# NT_SolarModule3.net
KiCad netlist of a schematic drawn in EAGLE
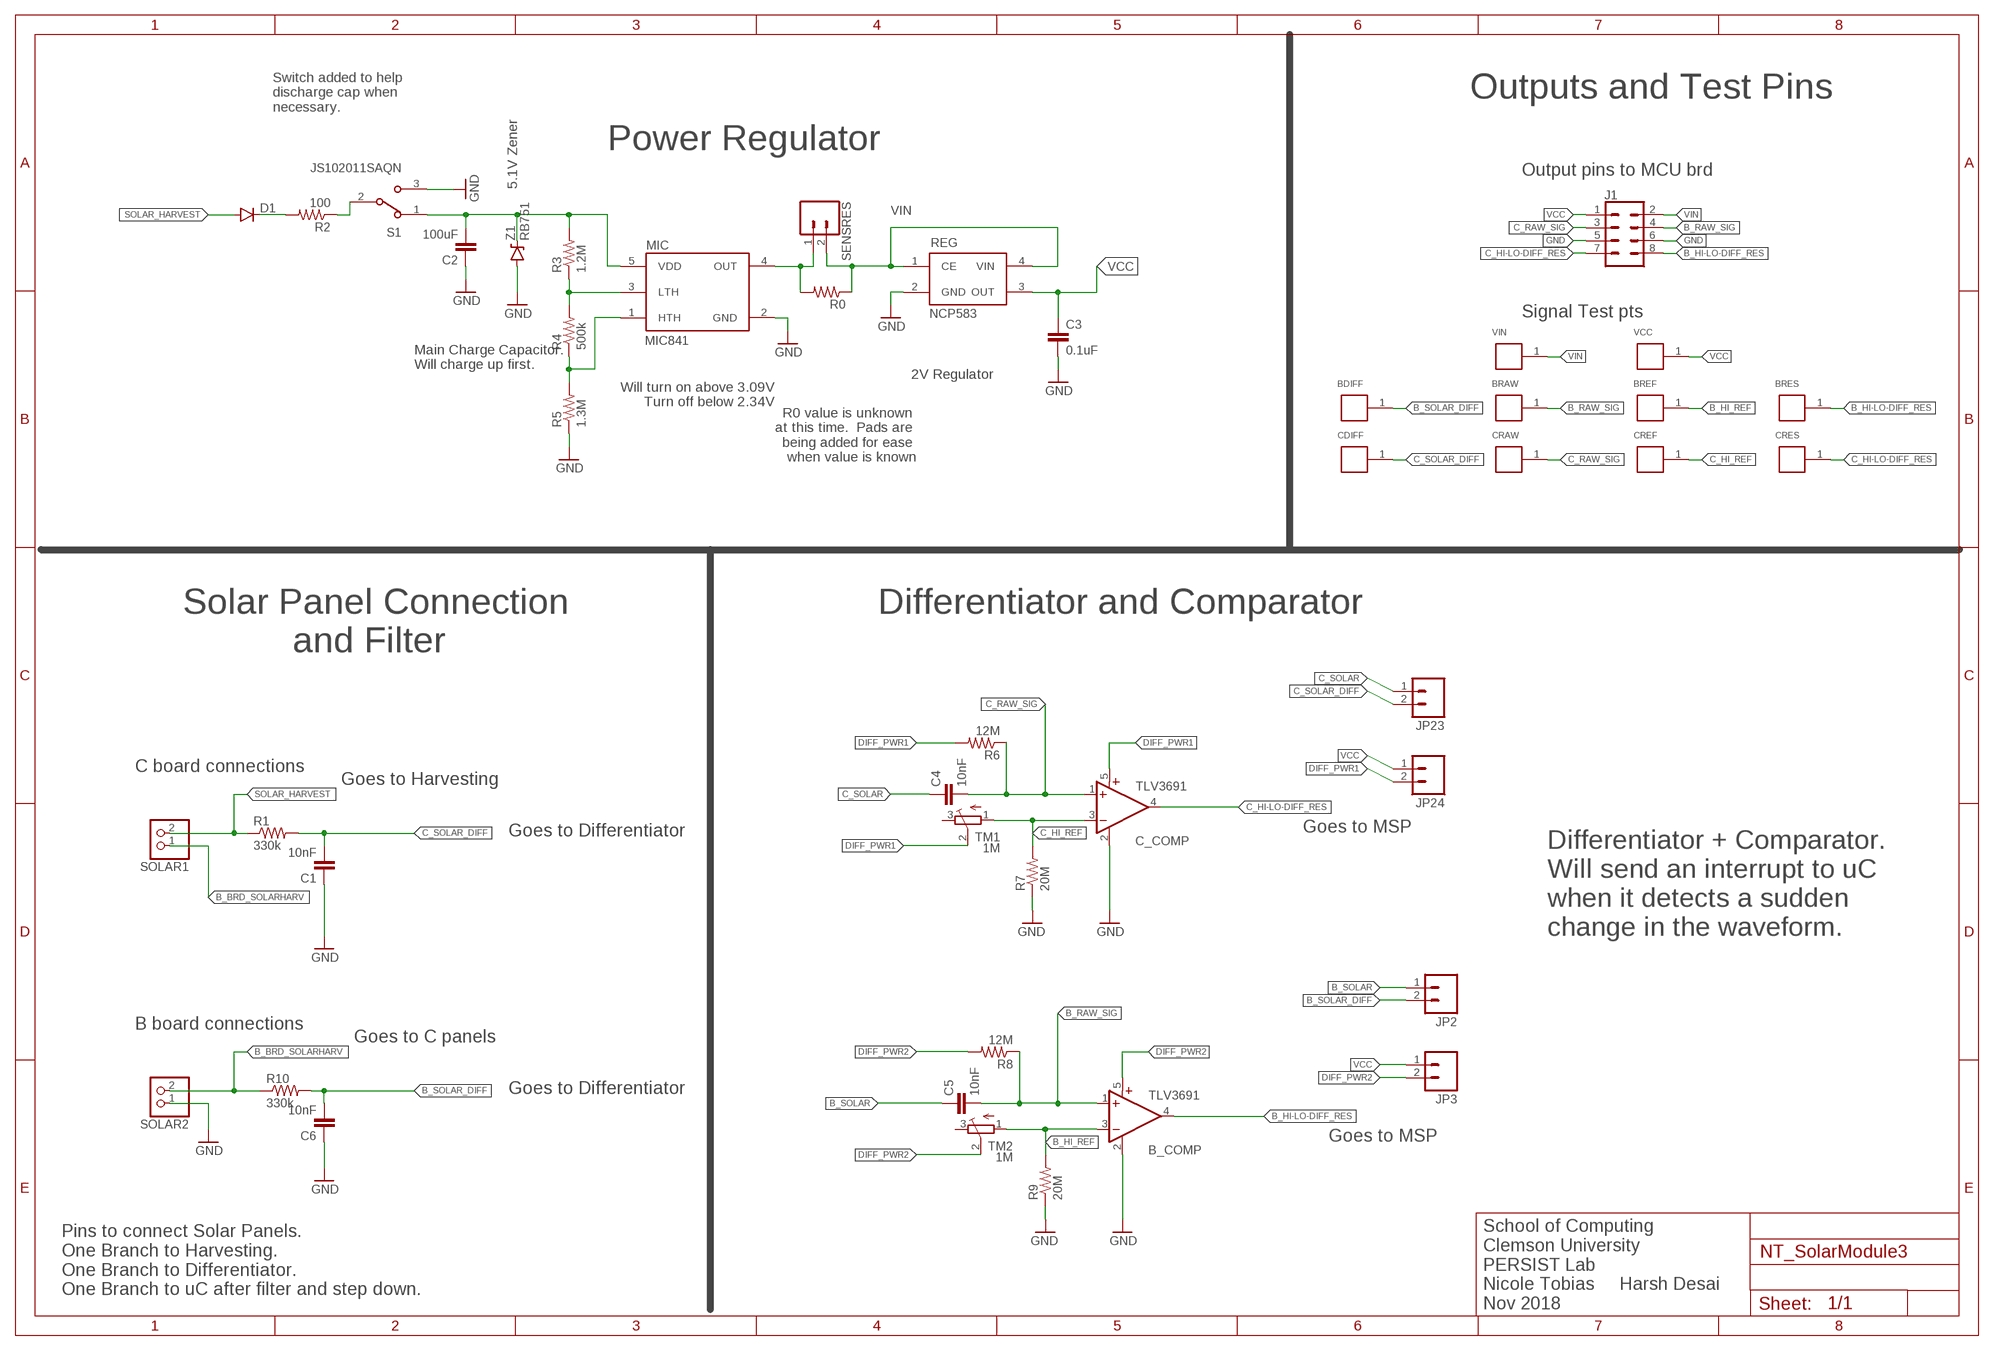
[diagram p0: schematic, sheet 1]

(export (version "E")
  (design (tool "Eeschema 10.0.6"))
  (components
    (comp (ref "BDIFF")
      (value "RCU-0C")
      (footprint "eagle-import:TE_RCU-0C")
      (fields
        (field (name "COMMENT") "RCU-0C _1625854-3_")
        (field (name "MF") "TE Connectivity")
        (field (name "TOLERANCE") "0%")
      )
      (libsource (lib "eagle-import") (part "RCU-0C"))
    )
    (comp (ref "BRAW")
      (value "RCU-0C")
      (footprint "eagle-import:TE_RCU-0C")
      (fields
        (field (name "COMMENT") "RCU-0C _1625854-3_")
        (field (name "MF") "TE Connectivity")
        (field (name "TOLERANCE") "0%")
      )
      (libsource (lib "eagle-import") (part "RCU-0C"))
    )
    (comp (ref "BREF")
      (value "RCU-0C")
      (footprint "eagle-import:TE_RCU-0C")
      (fields
        (field (name "COMMENT") "RCU-0C _1625854-3_")
        (field (name "MF") "TE Connectivity")
        (field (name "TOLERANCE") "0%")
      )
      (libsource (lib "eagle-import") (part "RCU-0C"))
    )
    (comp (ref "BRES")
      (value "RCU-0C")
      (footprint "eagle-import:TE_RCU-0C")
      (fields
        (field (name "COMMENT") "RCU-0C _1625854-3_")
        (field (name "MF") "TE Connectivity")
        (field (name "TOLERANCE") "0%")
      )
      (libsource (lib "eagle-import") (part "RCU-0C"))
    )
    (comp (ref "B_COMP")
      (value "TLV3691")
      (footprint "eagle-import:SC70-5")
      (libsource (lib "eagle-import") (part "TLV3691"))
    )
    (comp (ref "C1")
      (value "10nF")
      (footprint "eagle-import:0603-CAP")
      (libsource (lib "eagle-import") (part "CAP0603-CAP"))
    )
    (comp (ref "C2")
      (value "100uF")
      (footprint "eagle-import:0603-CAP")
      (libsource (lib "eagle-import") (part "CAP0603-CAP"))
    )
    (comp (ref "C3")
      (value "0.1uF")
      (footprint "eagle-import:0603-CAP")
      (libsource (lib "eagle-import") (part "CAP0603-CAP"))
    )
    (comp (ref "C4")
      (value "10nF")
      (footprint "eagle-import:0603-CAP")
      (libsource (lib "eagle-import") (part "CAP0603-CAP"))
    )
    (comp (ref "C5")
      (value "10nF")
      (footprint "eagle-import:0603-CAP")
      (libsource (lib "eagle-import") (part "CAP0603-CAP"))
    )
    (comp (ref "C6")
      (value "10nF")
      (footprint "eagle-import:0603-CAP")
      (libsource (lib "eagle-import") (part "CAP0603-CAP"))
    )
    (comp (ref "CDIFF")
      (value "RCU-0C")
      (footprint "eagle-import:TE_RCU-0C")
      (fields
        (field (name "COMMENT") "RCU-0C _1625854-3_")
        (field (name "MF") "TE Connectivity")
        (field (name "TOLERANCE") "0%")
      )
      (libsource (lib "eagle-import") (part "RCU-0C"))
    )
    (comp (ref "CRAW")
      (value "RCU-0C")
      (footprint "eagle-import:TE_RCU-0C")
      (fields
        (field (name "COMMENT") "RCU-0C _1625854-3_")
        (field (name "MF") "TE Connectivity")
        (field (name "TOLERANCE") "0%")
      )
      (libsource (lib "eagle-import") (part "RCU-0C"))
    )
    (comp (ref "CREF")
      (value "RCU-0C")
      (footprint "eagle-import:TE_RCU-0C")
      (fields
        (field (name "COMMENT") "RCU-0C _1625854-3_")
        (field (name "MF") "TE Connectivity")
        (field (name "TOLERANCE") "0%")
      )
      (libsource (lib "eagle-import") (part "RCU-0C"))
    )
    (comp (ref "CRES")
      (value "RCU-0C")
      (footprint "eagle-import:TE_RCU-0C")
      (fields
        (field (name "COMMENT") "RCU-0C _1625854-3_")
        (field (name "MF") "TE Connectivity")
        (field (name "TOLERANCE") "0%")
      )
      (libsource (lib "eagle-import") (part "RCU-0C"))
    )
    (comp (ref "C_COMP")
      (value "TLV3691")
      (footprint "eagle-import:SC70-5")
      (libsource (lib "eagle-import") (part "TLV3691"))
    )
    (comp (ref "D1")
      (value "DIODESOD523")
      (footprint "eagle-import:SOD523")
      (libsource (lib "eagle-import") (part "DIODESOD523"))
    )
    (comp (ref "J1")
      (value "CONN_04X2")
      (footprint "eagle-import:2X4")
      (libsource (lib "eagle-import") (part "CONN_04X2"))
    )
    (comp (ref "JP2")
      (value "M02")
      (footprint "eagle-import:1X02-1.27MM")
      (libsource (lib "eagle-import") (part "M02"))
    )
    (comp (ref "JP3")
      (value "M02")
      (footprint "eagle-import:1X02-1.27MM")
      (libsource (lib "eagle-import") (part "M02"))
    )
    (comp (ref "JP23")
      (value "M02")
      (footprint "eagle-import:1X02-1.27MM")
      (libsource (lib "eagle-import") (part "M02"))
    )
    (comp (ref "JP24")
      (value "M02")
      (footprint "eagle-import:1X02-1.27MM")
      (libsource (lib "eagle-import") (part "M02"))
    )
    (comp (ref "MIC")
      (value "MIC841")
      (footprint "eagle-import:SC70-5")
      (libsource (lib "eagle-import") (part "MIC841"))
    )
    (comp (ref "R0")
      (value "RESISTOR0603")
      (footprint "eagle-import:0603-RES")
      (libsource (lib "eagle-import") (part "RESISTOR0603"))
    )
    (comp (ref "R1")
      (value "330k")
      (footprint "eagle-import:0603-RES")
      (libsource (lib "eagle-import") (part "RESISTOR0603"))
    )
    (comp (ref "R2")
      (value "100")
      (footprint "eagle-import:0603-RES")
      (libsource (lib "eagle-import") (part "RESISTOR0603"))
    )
    (comp (ref "R3")
      (value "1.2M")
      (footprint "eagle-import:0603-RES")
      (libsource (lib "eagle-import") (part "RESISTOR0603"))
    )
    (comp (ref "R4")
      (value "500k")
      (footprint "eagle-import:0603-RES")
      (libsource (lib "eagle-import") (part "RESISTOR0603"))
    )
    (comp (ref "R5")
      (value "1.3M")
      (footprint "eagle-import:0603-RES")
      (libsource (lib "eagle-import") (part "RESISTOR0603"))
    )
    (comp (ref "R6")
      (value "12M")
      (footprint "eagle-import:0603-RES")
      (libsource (lib "eagle-import") (part "RESISTOR0603"))
    )
    (comp (ref "R7")
      (value "20M")
      (footprint "eagle-import:0603-RES")
      (libsource (lib "eagle-import") (part "RESISTOR0603"))
    )
    (comp (ref "R8")
      (value "12M")
      (footprint "eagle-import:0603-RES")
      (libsource (lib "eagle-import") (part "RESISTOR0603"))
    )
    (comp (ref "R9")
      (value "20M")
      (footprint "eagle-import:0603-RES")
      (libsource (lib "eagle-import") (part "RESISTOR0603"))
    )
    (comp (ref "R10")
      (value "330k")
      (footprint "eagle-import:0603-RES")
      (libsource (lib "eagle-import") (part "RESISTOR0603"))
    )
    (comp (ref "REG")
      (value "NCP583")
      (footprint "eagle-import:SC82-AB_1PRIMARY")
      (libsource (lib "eagle-import") (part "NCP583"))
    )
    (comp (ref "S1")
      (value "JS102011SAQN")
      (footprint "eagle-import:SW_JS102011SAQN")
      (fields (field (name "MF") "C&K Components"))
      (libsource (lib "eagle-import") (part "JS102011SAQN"))
    )
    (comp (ref "SENSRES")
      (value "CONN_02")
      (footprint "eagle-import:1X02")
      (libsource (lib "eagle-import") (part "CONN_02"))
    )
    (comp (ref "SOLAR1")
      (value "PINHD-1X2")
      (footprint "eagle-import:1X02")
      (libsource (lib "eagle-import") (part "PINHD-1X2"))
    )
    (comp (ref "SOLAR2")
      (value "PINHD-1X2")
      (footprint "eagle-import:1X02")
      (libsource (lib "eagle-import") (part "PINHD-1X2"))
    )
    (comp (ref "TM1")
      (value "1M")
      (footprint "eagle-import:TC33X")
      (libsource (lib "eagle-import") (part "TRIMPOTTC33X"))
    )
    (comp (ref "TM2")
      (value "1M")
      (footprint "eagle-import:TC33X")
      (libsource (lib "eagle-import") (part "TRIMPOTTC33X"))
    )
    (comp (ref "VCC")
      (value "RCU-0C")
      (footprint "eagle-import:TE_RCU-0C")
      (fields
        (field (name "COMMENT") "RCU-0C _1625854-3_")
        (field (name "MF") "TE Connectivity")
        (field (name "TOLERANCE") "0%")
      )
      (libsource (lib "eagle-import") (part "RCU-0C"))
    )
    (comp (ref "VIN")
      (value "RCU-0C")
      (footprint "eagle-import:TE_RCU-0C")
      (fields
        (field (name "COMMENT") "RCU-0C _1625854-3_")
        (field (name "MF") "TE Connectivity")
        (field (name "TOLERANCE") "0%")
      )
      (libsource (lib "eagle-import") (part "RCU-0C"))
    )
    (comp (ref "Z1")
      (value "RB751")
      (footprint "eagle-import:SOD-523")
      (libsource (lib "eagle-import") (part "DIODE-ZENER"))
    )
  )
  (nets
    (net (code "1") (name "B_BRD_SOLARHARV") (class "Default")
      (node (ref "R10") (pin "1") (pinfunction "1_1") (pintype "passive"))
      (node (ref "SOLAR1") (pin "1") (pinfunction "1_1") (pintype "passive"))
      (node (ref "SOLAR2") (pin "2") (pinfunction "2_2") (pintype "passive"))
    )
    (net (code "2") (name "B_HI-LO-DIFF_RES") (class "Default")
      (node (ref "BRES") (pin "1") (pinfunction "1_1") (pintype "passive"))
      (node (ref "B_COMP") (pin "4") (pinfunction "OUT_4") (pintype "output"))
      (node (ref "J1") (pin "8") (pinfunction "8_8") (pintype "passive"))
    )
    (net (code "3") (name "B_HI_REF") (class "Default")
      (node (ref "BREF") (pin "1") (pinfunction "1_1") (pintype "passive"))
      (node (ref "B_COMP") (pin "3") (pinfunction "-IN_3") (pintype "input"))
      (node (ref "R9") (pin "2") (pinfunction "2_2") (pintype "passive"))
      (node (ref "TM2") (pin "1") (pinfunction "A_1") (pintype "passive"))
    )
    (net (code "4") (name "B_RAW_SIG") (class "Default")
      (node (ref "BRAW") (pin "1") (pinfunction "1_1") (pintype "passive"))
      (node (ref "B_COMP") (pin "1") (pinfunction "+IN_1") (pintype "input"))
      (node (ref "C5") (pin "2") (pinfunction "2_2") (pintype "passive"))
      (node (ref "J1") (pin "4") (pinfunction "4_4") (pintype "passive"))
      (node (ref "R8") (pin "1") (pinfunction "1_1") (pintype "passive"))
    )
    (net (code "5") (name "B_SOLAR") (class "Default")
      (node (ref "C5") (pin "1") (pinfunction "1_1") (pintype "passive"))
      (node (ref "JP2") (pin "1") (pinfunction "1_1") (pintype "passive"))
    )
    (net (code "6") (name "B_SOLAR_DIFF") (class "Default")
      (node (ref "BDIFF") (pin "1") (pinfunction "1_1") (pintype "passive"))
      (node (ref "C6") (pin "2") (pinfunction "2_2") (pintype "passive"))
      (node (ref "JP2") (pin "2") (pinfunction "2_2") (pintype "passive"))
      (node (ref "R10") (pin "2") (pinfunction "2_2") (pintype "passive"))
    )
    (net (code "7") (name "C_HI-LO-DIFF_RES") (class "Default")
      (node (ref "CRES") (pin "1") (pinfunction "1_1") (pintype "passive"))
      (node (ref "C_COMP") (pin "4") (pinfunction "OUT_4") (pintype "output"))
      (node (ref "J1") (pin "7") (pinfunction "7_7") (pintype "passive"))
    )
    (net (code "8") (name "C_HI_REF") (class "Default")
      (node (ref "CREF") (pin "1") (pinfunction "1_1") (pintype "passive"))
      (node (ref "C_COMP") (pin "3") (pinfunction "-IN_3") (pintype "input"))
      (node (ref "R7") (pin "2") (pinfunction "2_2") (pintype "passive"))
      (node (ref "TM1") (pin "1") (pinfunction "A_1") (pintype "passive"))
    )
    (net (code "9") (name "C_RAW_SIG") (class "Default")
      (node (ref "C4") (pin "2") (pinfunction "2_2") (pintype "passive"))
      (node (ref "CRAW") (pin "1") (pinfunction "1_1") (pintype "passive"))
      (node (ref "C_COMP") (pin "1") (pinfunction "+IN_1") (pintype "input"))
      (node (ref "J1") (pin "3") (pinfunction "3_3") (pintype "passive"))
      (node (ref "R6") (pin "1") (pinfunction "1_1") (pintype "passive"))
    )
    (net (code "10") (name "C_SOLAR") (class "Default")
      (node (ref "C4") (pin "1") (pinfunction "1_1") (pintype "passive"))
      (node (ref "JP23") (pin "1") (pinfunction "1_1") (pintype "passive"))
    )
    (net (code "11") (name "C_SOLAR_DIFF") (class "Default")
      (node (ref "C1") (pin "2") (pinfunction "2_2") (pintype "passive"))
      (node (ref "CDIFF") (pin "1") (pinfunction "1_1") (pintype "passive"))
      (node (ref "JP23") (pin "2") (pinfunction "2_2") (pintype "passive"))
      (node (ref "R1") (pin "2") (pinfunction "2_2") (pintype "passive"))
    )
    (net (code "12") (name "DIFF_PWR1") (class "Default")
      (node (ref "C_COMP") (pin "5") (pinfunction "V+_5") (pintype "power_in"))
      (node (ref "JP24") (pin "2") (pinfunction "2_2") (pintype "passive"))
      (node (ref "R6") (pin "2") (pinfunction "2_2") (pintype "passive"))
      (node (ref "TM1") (pin "2") (pinfunction "S_2") (pintype "passive"))
    )
    (net (code "13") (name "DIFF_PWR2") (class "Default")
      (node (ref "B_COMP") (pin "5") (pinfunction "V+_5") (pintype "power_in"))
      (node (ref "JP3") (pin "2") (pinfunction "2_2") (pintype "passive"))
      (node (ref "R8") (pin "2") (pinfunction "2_2") (pintype "passive"))
      (node (ref "TM2") (pin "2") (pinfunction "S_2") (pintype "passive"))
    )
    (net (code "14") (name "GND") (class "Default")
      (node (ref "B_COMP") (pin "2") (pinfunction "GND_2") (pintype "power_in"))
      (node (ref "C1") (pin "1") (pinfunction "1_1") (pintype "passive"))
      (node (ref "C2") (pin "1") (pinfunction "1_1") (pintype "passive"))
      (node (ref "C3") (pin "2") (pinfunction "2_2") (pintype "passive"))
      (node (ref "C6") (pin "1") (pinfunction "1_1") (pintype "passive"))
      (node (ref "C_COMP") (pin "2") (pinfunction "GND_2") (pintype "power_in"))
      (node (ref "J1") (pin "5") (pinfunction "5_5") (pintype "passive"))
      (node (ref "J1") (pin "6") (pinfunction "6_6") (pintype "passive"))
      (node (ref "MIC") (pin "2") (pinfunction "GND_2") (pintype "bidirectional"))
      (node (ref "R5") (pin "1") (pinfunction "1_1") (pintype "passive"))
      (node (ref "R7") (pin "1") (pinfunction "1_1") (pintype "passive"))
      (node (ref "R9") (pin "1") (pinfunction "1_1") (pintype "passive"))
      (node (ref "REG") (pin "2") (pinfunction "GND_2") (pintype "bidirectional"))
      (node (ref "S1") (pin "3") (pinfunction "3_3") (pintype "passive"))
      (node (ref "SOLAR2") (pin "1") (pinfunction "1_1") (pintype "passive"))
      (node (ref "Z1") (pin "ANODE") (pinfunction "A_ANODE") (pintype "passive"))
    )
    (net (code "15") (name "Net-(D1-PadC)") (class "Default")
      (node (ref "D1") (pin "C") (pinfunction "C_C") (pintype "passive"))
      (node (ref "R2") (pin "2") (pinfunction "2_2") (pintype "passive"))
    )
    (net (code "16") (name "Net-(MIC-HTH)") (class "Default")
      (node (ref "MIC") (pin "1") (pinfunction "HTH_1") (pintype "bidirectional"))
      (node (ref "R4") (pin "1") (pinfunction "1_1") (pintype "passive"))
      (node (ref "R5") (pin "2") (pinfunction "2_2") (pintype "passive"))
    )
    (net (code "17") (name "Net-(MIC-LTH)") (class "Default")
      (node (ref "MIC") (pin "3") (pinfunction "LTH_3") (pintype "bidirectional"))
      (node (ref "R3") (pin "1") (pinfunction "1_1") (pintype "passive"))
      (node (ref "R4") (pin "2") (pinfunction "2_2") (pintype "passive"))
    )
    (net (code "18") (name "Net-(MIC-OUT)") (class "Default")
      (node (ref "MIC") (pin "4") (pinfunction "OUT_4") (pintype "bidirectional"))
      (node (ref "R0") (pin "2") (pinfunction "2_2") (pintype "passive"))
      (node (ref "SENSRES") (pin "1") (pinfunction "1_1") (pintype "passive"))
    )
    (net (code "19") (name "Net-(MIC-VDD)") (class "Default")
      (node (ref "C2") (pin "2") (pinfunction "2_2") (pintype "passive"))
      (node (ref "MIC") (pin "5") (pinfunction "VDD_5") (pintype "bidirectional"))
      (node (ref "R3") (pin "2") (pinfunction "2_2") (pintype "passive"))
      (node (ref "S1") (pin "1") (pinfunction "1_1") (pintype "passive"))
      (node (ref "Z1") (pin "CATHODE") (pinfunction "C_CATHODE") (pintype "passive"))
    )
    (net (code "20") (name "Net-(R2-Pad1)") (class "Default")
      (node (ref "R2") (pin "1") (pinfunction "1_1") (pintype "passive"))
      (node (ref "S1") (pin "2") (pinfunction "2_2") (pintype "passive"))
    )
    (net (code "21") (name "SOLAR_HARVEST") (class "Default")
      (node (ref "D1") (pin "A") (pinfunction "A_A") (pintype "passive"))
      (node (ref "R1") (pin "1") (pinfunction "1_1") (pintype "passive"))
      (node (ref "SOLAR1") (pin "2") (pinfunction "2_2") (pintype "passive"))
    )
    (net (code "22") (name "VCC") (class "Default")
      (node (ref "C3") (pin "1") (pinfunction "1_1") (pintype "passive"))
      (node (ref "J1") (pin "1") (pinfunction "1_1") (pintype "passive"))
      (node (ref "JP24") (pin "1") (pinfunction "1_1") (pintype "passive"))
      (node (ref "JP3") (pin "1") (pinfunction "1_1") (pintype "passive"))
      (node (ref "REG") (pin "3") (pinfunction "OUT_3") (pintype "bidirectional"))
      (node (ref "VCC") (pin "1") (pinfunction "1_1") (pintype "passive"))
    )
    (net (code "23") (name "VIN") (class "Default")
      (node (ref "J1") (pin "2") (pinfunction "2_2") (pintype "passive"))
      (node (ref "R0") (pin "1") (pinfunction "1_1") (pintype "passive"))
      (node (ref "REG") (pin "1") (pinfunction "CE_1") (pintype "bidirectional"))
      (node (ref "REG") (pin "4") (pinfunction "VIN_4") (pintype "bidirectional"))
      (node (ref "SENSRES") (pin "2") (pinfunction "2_2") (pintype "passive"))
      (node (ref "VIN") (pin "1") (pinfunction "1_1") (pintype "passive"))
    )
    (net (code "24") (name "unconnected-(TM1-E-Pad3)") (class "Default")
      (node (ref "TM1") (pin "3") (pinfunction "E_3") (pintype "passive"))
    )
    (net (code "25") (name "unconnected-(TM2-E-Pad3)") (class "Default")
      (node (ref "TM2") (pin "3") (pinfunction "E_3") (pintype "passive"))
    )
  )
)
